# core.net
KiCad netlist of a schematic drawn in Altium Designer
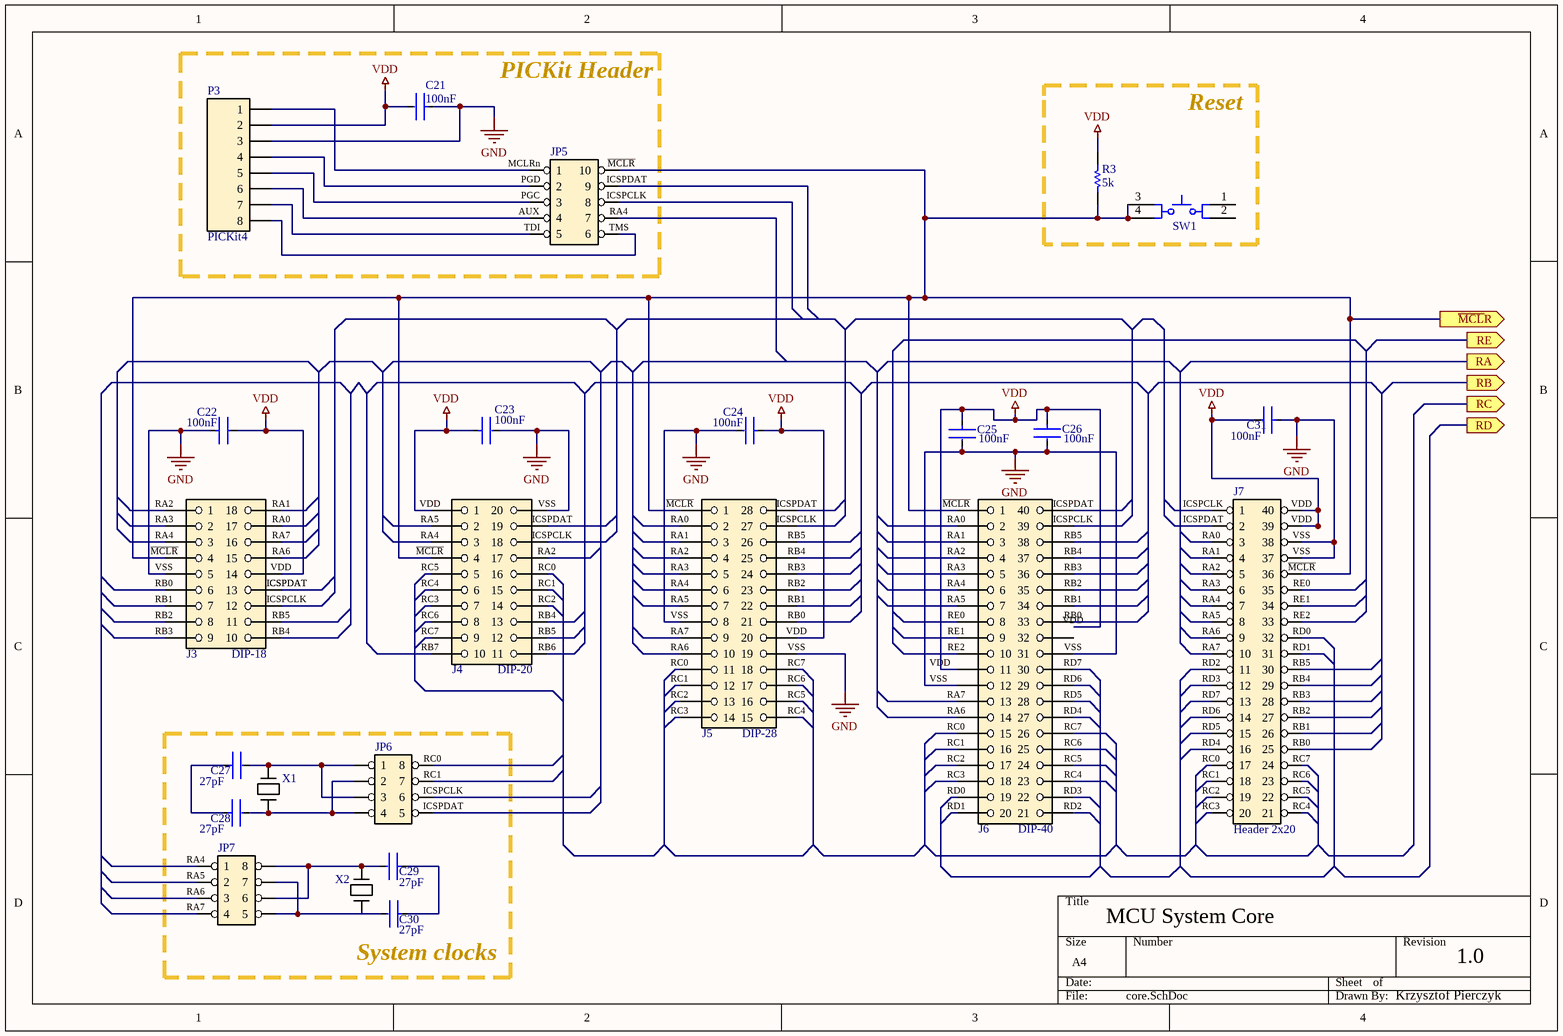
[diagram p0: core.SchDoc]

(export (version "E")
  (design (tool "Eeschema 10.0.6"))
  (components
    (comp (ref "C21")
      (value "100nF")
      (footprint "FP-C0805C-DN-MFG")
      (description "CAP CER 1000PF 50V C0G/NP0 0805")
      (fields
        (field (name "MANUFACTURER") "KEMET")
        (field (name "OCTOPART") "https://octopart.com/c0805c102j5gactu-kemet-97757")
      )
      (libsource (lib "Altium Content Vault") (part "b4654b650e69147ec39a6b967a45e02"))
    )
    (comp (ref "C22")
      (value "100nF")
      (footprint "FP-C0805C-DN-MFG")
      (description "CAP CER 1000PF 50V C0G/NP0 0805")
      (fields
        (field (name "MANUFACTURER") "KEMET")
        (field (name "OCTOPART") "https://octopart.com/c0805c102j5gactu-kemet-97757")
      )
      (libsource (lib "Altium Content Vault") (part "b4654b650e69147ec39a6b967a45e02"))
    )
    (comp (ref "C23")
      (value "100nF")
      (footprint "FP-C0805C-DN-MFG")
      (description "CAP CER 1000PF 50V C0G/NP0 0805")
      (fields
        (field (name "MANUFACTURER") "KEMET")
        (field (name "OCTOPART") "https://octopart.com/c0805c102j5gactu-kemet-97757")
      )
      (libsource (lib "Altium Content Vault") (part "b4654b650e69147ec39a6b967a45e02"))
    )
    (comp (ref "C24")
      (value "100nF")
      (footprint "FP-C0805C-DN-MFG")
      (description "CAP CER 1000PF 50V C0G/NP0 0805")
      (fields
        (field (name "MANUFACTURER") "KEMET")
        (field (name "OCTOPART") "https://octopart.com/c0805c102j5gactu-kemet-97757")
      )
      (libsource (lib "Altium Content Vault") (part "b4654b650e69147ec39a6b967a45e02"))
    )
    (comp (ref "C25")
      (value "100nF")
      (footprint "FP-C0805C-DN-MFG")
      (description "CAP CER 1000PF 50V C0G/NP0 0805")
      (fields
        (field (name "MANUFACTURER") "KEMET")
        (field (name "OCTOPART") "https://octopart.com/c0805c102j5gactu-kemet-97757")
      )
      (libsource (lib "Altium Content Vault") (part "b4654b650e69147ec39a6b967a45e02"))
    )
    (comp (ref "C26")
      (value "100nF")
      (footprint "FP-C0805C-DN-MFG")
      (description "CAP CER 1000PF 50V C0G/NP0 0805")
      (fields
        (field (name "MANUFACTURER") "KEMET")
        (field (name "OCTOPART") "https://octopart.com/c0805c102j5gactu-kemet-97757")
      )
      (libsource (lib "Altium Content Vault") (part "b4654b650e69147ec39a6b967a45e02"))
    )
    (comp (ref "C27")
      (value "27pF")
      (footprint "FP-C0805C-DN-MFG")
      (description "CAP CER 1000PF 50V C0G/NP0 0805")
      (fields
        (field (name "MANUFACTURER") "KEMET")
        (field (name "OCTOPART") "https://octopart.com/c0805c102j5gactu-kemet-97757")
      )
      (libsource (lib "Altium Content Vault") (part "b4654b650e69147ec39a6b967a45e02"))
    )
    (comp (ref "C28")
      (value "27pF")
      (footprint "FP-C0805C-DN-MFG")
      (description "CAP CER 1000PF 50V C0G/NP0 0805")
      (fields
        (field (name "MANUFACTURER") "KEMET")
        (field (name "OCTOPART") "https://octopart.com/c0805c102j5gactu-kemet-97757")
      )
      (libsource (lib "Altium Content Vault") (part "b4654b650e69147ec39a6b967a45e02"))
    )
    (comp (ref "C29")
      (value "27pF")
      (footprint "FP-C0805C-DN-MFG")
      (description "CAP CER 1000PF 50V C0G/NP0 0805")
      (fields
        (field (name "MANUFACTURER") "KEMET")
        (field (name "OCTOPART") "https://octopart.com/c0805c102j5gactu-kemet-97757")
      )
      (libsource (lib "Altium Content Vault") (part "b4654b650e69147ec39a6b967a45e02"))
    )
    (comp (ref "C30")
      (value "27pF")
      (footprint "FP-C0805C-DN-MFG")
      (description "CAP CER 1000PF 50V C0G/NP0 0805")
      (fields
        (field (name "MANUFACTURER") "KEMET")
        (field (name "OCTOPART") "https://octopart.com/c0805c102j5gactu-kemet-97757")
      )
      (libsource (lib "Altium Content Vault") (part "b4654b650e69147ec39a6b967a45e02"))
    )
    (comp (ref "C31")
      (value "100nF")
      (footprint "FP-C0805C-DN-MFG")
      (description "CAP CER 1000PF 50V C0G/NP0 0805")
      (fields
        (field (name "MANUFACTURER") "KEMET")
        (field (name "OCTOPART") "https://octopart.com/c0805c102j5gactu-kemet-97757")
      )
      (libsource (lib "Altium Content Vault") (part "b4654b650e69147ec39a6b967a45e02"))
    )
    (comp (ref "J3") (value "DIP-18") (libsource (lib "miscellanea") (part "DIP-18")))
    (comp (ref "J4") (value "DIP-20") (libsource (lib "miscellanea") (part "DIP-20")))
    (comp (ref "J5") (value "DIP-28") (libsource (lib "miscellanea") (part "DIP-28")))
    (comp (ref "J6") (value "DIP-40") (libsource (lib "miscellanea") (part "DIP-40")))
    (comp (ref "J7") (value "Header 2x20") (libsource (lib "miscellanea") (part "Header 2x20")))
    (comp (ref "JP5") (value "Header 2x5") (libsource (lib "miscellanea") (part "Header 2x5")))
    (comp (ref "JP6") (value "Header 2x4") (libsource (lib "miscellanea") (part "Header 2x4")))
    (comp (ref "JP7") (value "Header 2x4") (libsource (lib "miscellanea") (part "Header 2x4")))
    (comp (ref "P3") (value "PICKit4") (libsource (lib "miscellanea") (part "Header 1x8 A")))
    (comp (ref "R3")
      (value "CRCW0805150RFKEA")
      (footprint "RESC2013X50X30ML20T20")
      (fields (field (name "MANUFACTURER") "Vishay Dale") (field (name "RESISTANCE") "5k"))
      (libsource (lib "Altium Content Vault") (part "RES"))
    )
    (comp (ref "SW1")
      (value "4-1437565-1")
      (footprint "TECO-4-1437565-1_V")
      (description "Tactile Switch, 50 mA, 12 VDC, -20 to 85 degC, 4-Pin SMD, RoHS, Bulk")
      (fields (field (name "MANUFACTURER") "TEConnectivity/AMPBrand"))
      (libsource (lib "Altium Content Vault") (part "SW-SPST-NO-4"))
    )
    (comp (ref "X1") (value "HC49SM") (libsource (lib "miscellanea") (part "HC49SM")))
    (comp (ref "X2") (value "HC49SM") (libsource (lib "") (part "HC49SM_1")))
  )
  (nets
    (net (code "1") (name "/ICSPCLK") (class "Default")
      (node (ref "J3") (pin "12") (pinfunction "12_12") (pintype "passive"))
      (node (ref "J4") (pin "18") (pinfunction "18_18") (pintype "passive"))
      (node (ref "J5") (pin "27") (pinfunction "27_27") (pintype "passive"))
      (node (ref "J6") (pin "39") (pinfunction "39_39") (pintype "passive"))
      (node (ref "J7") (pin "1") (pinfunction "1_1") (pintype "passive"))
      (node (ref "JP5") (pin "8") (pinfunction "8_8") (pintype "passive"))
      (node (ref "JP6") (pin "6") (pinfunction "6_6") (pintype "passive"))
    )
    (net (code "2") (name "/ICSPDAT") (class "Default")
      (node (ref "J3") (pin "13") (pinfunction "13_13") (pintype "passive"))
      (node (ref "J4") (pin "19") (pinfunction "19_19") (pintype "passive"))
      (node (ref "J5") (pin "28") (pinfunction "28_28") (pintype "passive"))
      (node (ref "J6") (pin "40") (pinfunction "40_40") (pintype "passive"))
      (node (ref "J7") (pin "2") (pinfunction "2_2") (pintype "passive"))
      (node (ref "JP5") (pin "9") (pinfunction "9_9") (pintype "passive"))
      (node (ref "JP6") (pin "5") (pinfunction "5_5") (pintype "passive"))
    )
    (net (code "4") (name "/RA0") (class "Default")
      (node (ref "J3") (pin "17") (pinfunction "17_17") (pintype "passive"))
      (node (ref "J5") (pin "2") (pinfunction "2_2") (pintype "passive"))
      (node (ref "J6") (pin "2") (pinfunction "2_2") (pintype "passive"))
      (node (ref "J7") (pin "3") (pinfunction "3_3") (pintype "passive"))
    )
    (net (code "5") (name "/RA1") (class "Default")
      (node (ref "J3") (pin "18") (pinfunction "18_18") (pintype "passive"))
      (node (ref "J5") (pin "3") (pinfunction "3_3") (pintype "passive"))
      (node (ref "J6") (pin "3") (pinfunction "3_3") (pintype "passive"))
      (node (ref "J7") (pin "4") (pinfunction "4_4") (pintype "passive"))
    )
    (net (code "6") (name "/RA2") (class "Default")
      (node (ref "J3") (pin "1") (pinfunction "1_1") (pintype "passive"))
      (node (ref "J4") (pin "17") (pinfunction "17_17") (pintype "passive"))
      (node (ref "J5") (pin "4") (pinfunction "4_4") (pintype "passive"))
      (node (ref "J6") (pin "4") (pinfunction "4_4") (pintype "passive"))
      (node (ref "J7") (pin "5") (pinfunction "5_5") (pintype "passive"))
    )
    (net (code "7") (name "/RA3") (class "Default")
      (node (ref "J3") (pin "2") (pinfunction "2_2") (pintype "passive"))
      (node (ref "J5") (pin "5") (pinfunction "5_5") (pintype "passive"))
      (node (ref "J6") (pin "5") (pinfunction "5_5") (pintype "passive"))
      (node (ref "J7") (pin "6") (pinfunction "6_6") (pintype "passive"))
    )
    (net (code "8") (name "/RA4") (class "Default")
      (node (ref "J3") (pin "3") (pinfunction "3_3") (pintype "passive"))
      (node (ref "J4") (pin "3") (pinfunction "3_3") (pintype "passive"))
      (node (ref "J5") (pin "6") (pinfunction "6_6") (pintype "passive"))
      (node (ref "J6") (pin "6") (pinfunction "6_6") (pintype "passive"))
      (node (ref "J7") (pin "7") (pinfunction "7_7") (pintype "passive"))
      (node (ref "JP5") (pin "7") (pinfunction "7_7") (pintype "passive"))
      (node (ref "JP7") (pin "1") (pinfunction "1_1") (pintype "passive"))
    )
    (net (code "9") (name "/RA5") (class "Default")
      (node (ref "J4") (pin "2") (pinfunction "2_2") (pintype "passive"))
      (node (ref "J5") (pin "7") (pinfunction "7_7") (pintype "passive"))
      (node (ref "J6") (pin "7") (pinfunction "7_7") (pintype "passive"))
      (node (ref "J7") (pin "8") (pinfunction "8_8") (pintype "passive"))
      (node (ref "JP7") (pin "2") (pinfunction "2_2") (pintype "passive"))
    )
    (net (code "10") (name "/RA6") (class "Default")
      (node (ref "J3") (pin "15") (pinfunction "15_15") (pintype "passive"))
      (node (ref "J5") (pin "10") (pinfunction "10_10") (pintype "passive"))
      (node (ref "J6") (pin "14") (pinfunction "14_14") (pintype "passive"))
      (node (ref "J7") (pin "9") (pinfunction "9_9") (pintype "passive"))
      (node (ref "JP7") (pin "3") (pinfunction "3_3") (pintype "passive"))
    )
    (net (code "11") (name "/RA7") (class "Default")
      (node (ref "J3") (pin "16") (pinfunction "16_16") (pintype "passive"))
      (node (ref "J5") (pin "9") (pinfunction "9_9") (pintype "passive"))
      (node (ref "J6") (pin "13") (pinfunction "13_13") (pintype "passive"))
      (node (ref "J7") (pin "10") (pinfunction "10_10") (pintype "passive"))
      (node (ref "JP7") (pin "4") (pinfunction "4_4") (pintype "passive"))
    )
    (net (code "13") (name "/RB0") (class "Default")
      (node (ref "J3") (pin "6") (pinfunction "6_6") (pintype "passive"))
      (node (ref "J5") (pin "21") (pinfunction "21_21") (pintype "passive"))
      (node (ref "J6") (pin "33") (pinfunction "33_33") (pintype "passive"))
      (node (ref "J7") (pin "25") (pinfunction "25_25") (pintype "passive"))
    )
    (net (code "14") (name "/RB1") (class "Default")
      (node (ref "J3") (pin "7") (pinfunction "7_7") (pintype "passive"))
      (node (ref "J5") (pin "22") (pinfunction "22_22") (pintype "passive"))
      (node (ref "J6") (pin "34") (pinfunction "34_34") (pintype "passive"))
      (node (ref "J7") (pin "26") (pinfunction "26_26") (pintype "passive"))
    )
    (net (code "15") (name "/RB2") (class "Default")
      (node (ref "J3") (pin "8") (pinfunction "8_8") (pintype "passive"))
      (node (ref "J5") (pin "23") (pinfunction "23_23") (pintype "passive"))
      (node (ref "J6") (pin "35") (pinfunction "35_35") (pintype "passive"))
      (node (ref "J7") (pin "27") (pinfunction "27_27") (pintype "passive"))
    )
    (net (code "16") (name "/RB3") (class "Default")
      (node (ref "J3") (pin "9") (pinfunction "9_9") (pintype "passive"))
      (node (ref "J5") (pin "24") (pinfunction "24_24") (pintype "passive"))
      (node (ref "J6") (pin "36") (pinfunction "36_36") (pintype "passive"))
      (node (ref "J7") (pin "28") (pinfunction "28_28") (pintype "passive"))
    )
    (net (code "17") (name "/RB4") (class "Default")
      (node (ref "J3") (pin "10") (pinfunction "10_10") (pintype "passive"))
      (node (ref "J4") (pin "13") (pinfunction "13_13") (pintype "passive"))
      (node (ref "J5") (pin "25") (pinfunction "25_25") (pintype "passive"))
      (node (ref "J6") (pin "37") (pinfunction "37_37") (pintype "passive"))
      (node (ref "J7") (pin "29") (pinfunction "29_29") (pintype "passive"))
    )
    (net (code "18") (name "/RB5") (class "Default")
      (node (ref "J3") (pin "11") (pinfunction "11_11") (pintype "passive"))
      (node (ref "J4") (pin "12") (pinfunction "12_12") (pintype "passive"))
      (node (ref "J5") (pin "26") (pinfunction "26_26") (pintype "passive"))
      (node (ref "J6") (pin "38") (pinfunction "38_38") (pintype "passive"))
      (node (ref "J7") (pin "30") (pinfunction "30_30") (pintype "passive"))
    )
    (net (code "19") (name "/RB6") (class "Default")
      (node (ref "J4") (pin "11") (pinfunction "11_11") (pintype "passive"))
    )
    (net (code "20") (name "/RB7") (class "Default")
      (node (ref "J4") (pin "10") (pinfunction "10_10") (pintype "passive"))
    )
    (net (code "22") (name "/RC0") (class "Default")
      (node (ref "J4") (pin "16") (pinfunction "16_16") (pintype "passive"))
      (node (ref "J5") (pin "11") (pinfunction "11_11") (pintype "passive"))
      (node (ref "J6") (pin "15") (pinfunction "15_15") (pintype "passive"))
      (node (ref "J7") (pin "17") (pinfunction "17_17") (pintype "passive"))
      (node (ref "JP6") (pin "8") (pinfunction "8_8") (pintype "passive"))
    )
    (net (code "23") (name "/RC1") (class "Default")
      (node (ref "J4") (pin "15") (pinfunction "15_15") (pintype "passive"))
      (node (ref "J5") (pin "12") (pinfunction "12_12") (pintype "passive"))
      (node (ref "J6") (pin "16") (pinfunction "16_16") (pintype "passive"))
      (node (ref "J7") (pin "18") (pinfunction "18_18") (pintype "passive"))
      (node (ref "JP6") (pin "7") (pinfunction "7_7") (pintype "passive"))
    )
    (net (code "24") (name "/RC2") (class "Default")
      (node (ref "J4") (pin "14") (pinfunction "14_14") (pintype "passive"))
      (node (ref "J5") (pin "13") (pinfunction "13_13") (pintype "passive"))
      (node (ref "J6") (pin "17") (pinfunction "17_17") (pintype "passive"))
      (node (ref "J7") (pin "19") (pinfunction "19_19") (pintype "passive"))
    )
    (net (code "25") (name "/RC3") (class "Default")
      (node (ref "J4") (pin "7") (pinfunction "7_7") (pintype "passive"))
      (node (ref "J5") (pin "14") (pinfunction "14_14") (pintype "passive"))
      (node (ref "J6") (pin "18") (pinfunction "18_18") (pintype "passive"))
      (node (ref "J7") (pin "20") (pinfunction "20_20") (pintype "passive"))
    )
    (net (code "26") (name "/RC4") (class "Default")
      (node (ref "J4") (pin "6") (pinfunction "6_6") (pintype "passive"))
      (node (ref "J5") (pin "15") (pinfunction "15_15") (pintype "passive"))
      (node (ref "J6") (pin "23") (pinfunction "23_23") (pintype "passive"))
      (node (ref "J7") (pin "21") (pinfunction "21_21") (pintype "passive"))
    )
    (net (code "27") (name "/RC5") (class "Default")
      (node (ref "J4") (pin "5") (pinfunction "5_5") (pintype "passive"))
      (node (ref "J5") (pin "16") (pinfunction "16_16") (pintype "passive"))
      (node (ref "J6") (pin "24") (pinfunction "24_24") (pintype "passive"))
      (node (ref "J7") (pin "22") (pinfunction "22_22") (pintype "passive"))
    )
    (net (code "28") (name "/RC6") (class "Default")
      (node (ref "J4") (pin "8") (pinfunction "8_8") (pintype "passive"))
      (node (ref "J5") (pin "17") (pinfunction "17_17") (pintype "passive"))
      (node (ref "J6") (pin "25") (pinfunction "25_25") (pintype "passive"))
      (node (ref "J7") (pin "23") (pinfunction "23_23") (pintype "passive"))
    )
    (net (code "29") (name "/RC7") (class "Default")
      (node (ref "J4") (pin "9") (pinfunction "9_9") (pintype "passive"))
      (node (ref "J5") (pin "18") (pinfunction "18_18") (pintype "passive"))
      (node (ref "J6") (pin "26") (pinfunction "26_26") (pintype "passive"))
      (node (ref "J7") (pin "24") (pinfunction "24_24") (pintype "passive"))
    )
    (net (code "31") (name "/RD0") (class "Default")
      (node (ref "J6") (pin "19") (pinfunction "19_19") (pintype "passive"))
      (node (ref "J7") (pin "32") (pinfunction "32_32") (pintype "passive"))
    )
    (net (code "32") (name "/RD1") (class "Default")
      (node (ref "J6") (pin "20") (pinfunction "20_20") (pintype "passive"))
      (node (ref "J7") (pin "31") (pinfunction "31_31") (pintype "passive"))
    )
    (net (code "33") (name "/RD2") (class "Default")
      (node (ref "J6") (pin "21") (pinfunction "21_21") (pintype "passive"))
      (node (ref "J7") (pin "11") (pinfunction "11_11") (pintype "passive"))
    )
    (net (code "34") (name "/RD3") (class "Default")
      (node (ref "J6") (pin "22") (pinfunction "22_22") (pintype "passive"))
      (node (ref "J7") (pin "12") (pinfunction "12_12") (pintype "passive"))
    )
    (net (code "35") (name "/RD4") (class "Default")
      (node (ref "J6") (pin "27") (pinfunction "27_27") (pintype "passive"))
      (node (ref "J7") (pin "16") (pinfunction "16_16") (pintype "passive"))
    )
    (net (code "36") (name "/RD5") (class "Default")
      (node (ref "J6") (pin "28") (pinfunction "28_28") (pintype "passive"))
      (node (ref "J7") (pin "15") (pinfunction "15_15") (pintype "passive"))
    )
    (net (code "37") (name "/RD6") (class "Default")
      (node (ref "J6") (pin "29") (pinfunction "29_29") (pintype "passive"))
      (node (ref "J7") (pin "14") (pinfunction "14_14") (pintype "passive"))
    )
    (net (code "38") (name "/RD7") (class "Default")
      (node (ref "J6") (pin "30") (pinfunction "30_30") (pintype "passive"))
      (node (ref "J7") (pin "13") (pinfunction "13_13") (pintype "passive"))
    )
    (net (code "40") (name "/RE0") (class "Default")
      (node (ref "J6") (pin "8") (pinfunction "8_8") (pintype "passive"))
      (node (ref "J7") (pin "35") (pinfunction "35_35") (pintype "passive"))
    )
    (net (code "41") (name "/RE1") (class "Default")
      (node (ref "J6") (pin "9") (pinfunction "9_9") (pintype "passive"))
      (node (ref "J7") (pin "34") (pinfunction "34_34") (pintype "passive"))
    )
    (net (code "42") (name "/RE2") (class "Default")
      (node (ref "J6") (pin "10") (pinfunction "10_10") (pintype "passive"))
      (node (ref "J7") (pin "33") (pinfunction "33_33") (pintype "passive"))
    )
    (net (code "43") (name "/~{MCLR}") (class "Default")
      (node (ref "J3") (pin "4") (pinfunction "4_4") (pintype "passive"))
      (node (ref "J4") (pin "4") (pinfunction "4_4") (pintype "passive"))
      (node (ref "J5") (pin "1") (pinfunction "1_1") (pintype "passive"))
      (node (ref "J6") (pin "1") (pinfunction "1_1") (pintype "passive"))
      (node (ref "J7") (pin "36") (pinfunction "36_36") (pintype "passive"))
      (node (ref "JP5") (pin "10") (pinfunction "10_10") (pintype "passive"))
      (node (ref "R3") (pin "1") (pinfunction "1_1") (pintype "passive"))
      (node (ref "SW1") (pin "3") (pinfunction "3_3") (pintype "passive"))
      (node (ref "SW1") (pin "4") (pinfunction "4_4") (pintype "passive"))
    )
    (net (code "44") (name "GND") (class "Default")
      (node (ref "C21") (pin "1") (pinfunction "1_1") (pintype "passive"))
      (node (ref "C22") (pin "1") (pinfunction "1_1") (pintype "passive"))
      (node (ref "C23") (pin "2") (pinfunction "2_2") (pintype "passive"))
      (node (ref "C24") (pin "2") (pinfunction "2_2") (pintype "passive"))
      (node (ref "C25") (pin "2") (pinfunction "2_2") (pintype "passive"))
      (node (ref "C26") (pin "2") (pinfunction "2_2") (pintype "passive"))
      (node (ref "C31") (pin "1") (pinfunction "1_1") (pintype "passive"))
      (node (ref "J3") (pin "5") (pinfunction "5_5") (pintype "passive"))
      (node (ref "J4") (pin "20") (pinfunction "20_20") (pintype "passive"))
      (node (ref "J5") (pin "19") (pinfunction "19_19") (pintype "passive"))
      (node (ref "J5") (pin "8") (pinfunction "8_8") (pintype "passive"))
      (node (ref "J6") (pin "12") (pinfunction "12_12") (pintype "passive"))
      (node (ref "J6") (pin "31") (pinfunction "31_31") (pintype "passive"))
      (node (ref "J7") (pin "37") (pinfunction "37_37") (pintype "passive"))
      (node (ref "J7") (pin "38") (pinfunction "38_38") (pintype "passive"))
      (node (ref "P3") (pin "3") (pinfunction "3_3") (pintype "passive"))
    )
    (net (code "45") (name "Net-(C27-Pad1)") (class "Default")
      (node (ref "C27") (pin "1") (pinfunction "1_1") (pintype "passive"))
      (node (ref "C28") (pin "1") (pinfunction "1_1") (pintype "passive"))
    )
    (net (code "46") (name "Net-(C27-Pad2)") (class "Default")
      (node (ref "C27") (pin "2") (pinfunction "2_2") (pintype "passive"))
      (node (ref "JP6") (pin "1") (pinfunction "1_1") (pintype "passive"))
      (node (ref "JP6") (pin "3") (pinfunction "3_3") (pintype "passive"))
      (node (ref "X1") (pin "2") (pinfunction "2_2") (pintype "passive"))
    )
    (net (code "47") (name "Net-(C28-Pad2)") (class "Default")
      (node (ref "C28") (pin "2") (pinfunction "2_2") (pintype "passive"))
      (node (ref "JP6") (pin "2") (pinfunction "2_2") (pintype "passive"))
      (node (ref "JP6") (pin "4") (pinfunction "4_4") (pintype "passive"))
      (node (ref "X1") (pin "2") (pinfunction "2_2") (pintype "passive"))
    )
    (net (code "48") (name "Net-(C29-Pad1)") (class "Default")
      (node (ref "C29") (pin "1") (pinfunction "1_1") (pintype "passive"))
      (node (ref "C30") (pin "1") (pinfunction "1_1") (pintype "passive"))
    )
    (net (code "49") (name "Net-(C29-Pad2)") (class "Default")
      (node (ref "C29") (pin "2") (pinfunction "2_2") (pintype "passive"))
      (node (ref "JP7") (pin "6") (pinfunction "6_6") (pintype "passive"))
      (node (ref "JP7") (pin "8") (pinfunction "8_8") (pintype "passive"))
      (node (ref "X2") (pin "2") (pinfunction "2_2") (pintype "passive"))
    )
    (net (code "50") (name "Net-(C30-Pad2)") (class "Default")
      (node (ref "C30") (pin "2") (pinfunction "2_2") (pintype "passive"))
      (node (ref "JP7") (pin "5") (pinfunction "5_5") (pintype "passive"))
      (node (ref "JP7") (pin "7") (pinfunction "7_7") (pintype "passive"))
      (node (ref "X2") (pin "2") (pinfunction "2_2") (pintype "passive"))
    )
    (net (code "51") (name "Net-(JP5-Pad1)") (class "Default")
      (node (ref "JP5") (pin "1") (pinfunction "1_1") (pintype "passive"))
      (node (ref "P3") (pin "1") (pinfunction "1_1") (pintype "passive"))
    )
    (net (code "52") (name "Net-(JP5-Pad2)") (class "Default")
      (node (ref "JP5") (pin "2") (pinfunction "2_2") (pintype "passive"))
      (node (ref "P3") (pin "4") (pinfunction "4_4") (pintype "passive"))
    )
    (net (code "53") (name "Net-(JP5-Pad3)") (class "Default")
      (node (ref "JP5") (pin "3") (pinfunction "3_3") (pintype "passive"))
      (node (ref "P3") (pin "5") (pinfunction "5_5") (pintype "passive"))
    )
    (net (code "54") (name "Net-(JP5-Pad4)") (class "Default")
      (node (ref "JP5") (pin "4") (pinfunction "4_4") (pintype "passive"))
      (node (ref "P3") (pin "6") (pinfunction "6_6") (pintype "passive"))
    )
    (net (code "55") (name "Net-(JP5-Pad5)") (class "Default")
      (node (ref "JP5") (pin "5") (pinfunction "5_5") (pintype "passive"))
      (node (ref "P3") (pin "7") (pinfunction "7_7") (pintype "passive"))
    )
    (net (code "56") (name "Net-(JP5-Pad6)") (class "Default")
      (node (ref "JP5") (pin "6") (pinfunction "6_6") (pintype "passive"))
      (node (ref "P3") (pin "8") (pinfunction "8_8") (pintype "passive"))
    )
    (net (code "57") (name "VDD") (class "Default")
      (node (ref "C21") (pin "2") (pinfunction "2_2") (pintype "passive"))
      (node (ref "C22") (pin "2") (pinfunction "2_2") (pintype "passive"))
      (node (ref "C23") (pin "1") (pinfunction "1_1") (pintype "passive"))
      (node (ref "C24") (pin "1") (pinfunction "1_1") (pintype "passive"))
      (node (ref "C25") (pin "1") (pinfunction "1_1") (pintype "passive"))
      (node (ref "C26") (pin "1") (pinfunction "1_1") (pintype "passive"))
      (node (ref "C31") (pin "2") (pinfunction "2_2") (pintype "passive"))
      (node (ref "J3") (pin "14") (pinfunction "14_14") (pintype "passive"))
      (node (ref "J4") (pin "1") (pinfunction "1_1") (pintype "passive"))
      (node (ref "J5") (pin "20") (pinfunction "20_20") (pintype "passive"))
      (node (ref "J6") (pin "11") (pinfunction "11_11") (pintype "passive"))
      (node (ref "J7") (pin "39") (pinfunction "39_39") (pintype "passive"))
      (node (ref "J7") (pin "40") (pinfunction "40_40") (pintype "passive"))
      (node (ref "P3") (pin "2") (pinfunction "2_2") (pintype "passive"))
      (node (ref "R3") (pin "2") (pinfunction "2_2") (pintype "passive"))
    )
    (net (code "58") (name "unconnected-(J6-Pad32)") (class "Default")
      (node (ref "J6") (pin "32") (pinfunction "32_32") (pintype "passive"))
    )
    (net (code "59") (name "unconnected-(SW1-Pad1)") (class "Default")
      (node (ref "SW1") (pin "1") (pinfunction "1_1") (pintype "passive"))
    )
    (net (code "60") (name "unconnected-(SW1-Pad2)") (class "Default")
      (node (ref "SW1") (pin "2") (pinfunction "2_2") (pintype "passive"))
    )
  )
)
